# CCM_0000.net
KiCad netlist of a schematic drawn in EAGLE
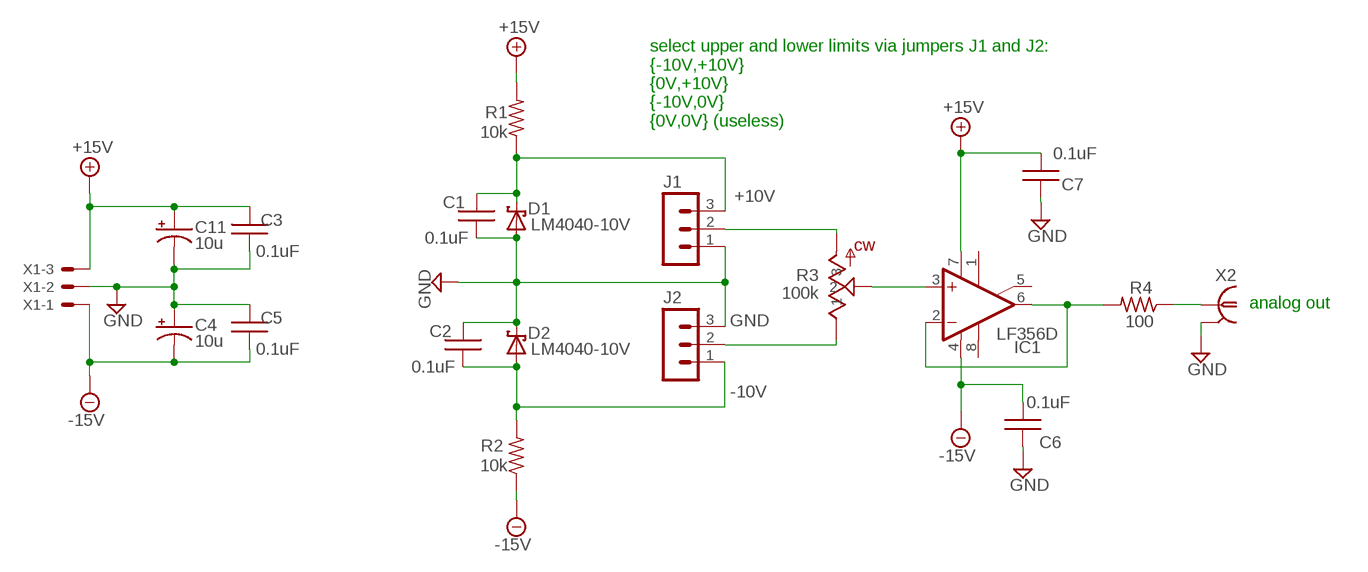
[diagram p0: schematic, sheet 1]

(export (version "E")
  (design (tool "Eeschema 10.0.6"))
  (components
    (comp (ref "C1")
      (value "0.1uF")
      (footprint "eagle-import:0603")
      (libsource (lib "eagle-import") (part "CAPACITOR0603"))
    )
    (comp (ref "C2")
      (value "0.1uF")
      (footprint "eagle-import:0603")
      (libsource (lib "eagle-import") (part "CAPACITOR0603"))
    )
    (comp (ref "C3")
      (value "0.1uF")
      (footprint "eagle-import:0603")
      (libsource (lib "eagle-import") (part "CAPACITOR0603"))
    )
    (comp (ref "C4")
      (value "10u")
      (footprint "eagle-import:EIA3216")
      (libsource (lib "eagle-import") (part "CAP_POL1206"))
    )
    (comp (ref "C5")
      (value "0.1uF")
      (footprint "eagle-import:0603")
      (libsource (lib "eagle-import") (part "CAPACITOR0603"))
    )
    (comp (ref "C6")
      (value "0.1uF")
      (footprint "eagle-import:0603")
      (libsource (lib "eagle-import") (part "CAPACITOR0603"))
    )
    (comp (ref "C7")
      (value "0.1uF")
      (footprint "eagle-import:0603")
      (libsource (lib "eagle-import") (part "CAPACITOR0603"))
    )
    (comp (ref "C11")
      (value "10u")
      (footprint "eagle-import:EIA3216")
      (libsource (lib "eagle-import") (part "CAP_POL1206"))
    )
    (comp (ref "D1")
      (value "LM4040-10V")
      (footprint "eagle-import:SOT23")
      (libsource (lib "eagle-import") (part "LM4040"))
    )
    (comp (ref "D2")
      (value "LM4040-10V")
      (footprint "eagle-import:SOT23")
      (libsource (lib "eagle-import") (part "LM4040"))
    )
    (comp (ref "IC1")
      (value "LF356D")
      (footprint "eagle-import:SO08")
      (libsource (lib "eagle-import") (part "LF356D"))
    )
    (comp (ref "J1")
      (value "MA03-1")
      (footprint "eagle-import:MA03-1")
      (libsource (lib "eagle-import") (part "MA03-1"))
    )
    (comp (ref "J2")
      (value "MA03-1")
      (footprint "eagle-import:MA03-1")
      (libsource (lib "eagle-import") (part "MA03-1"))
    )
    (comp (ref "R1")
      (value "10k")
      (footprint "eagle-import:0603")
      (libsource (lib "eagle-import") (part "RESISTOR0603"))
    )
    (comp (ref "R2")
      (value "10k")
      (footprint "eagle-import:0603")
      (libsource (lib "eagle-import") (part "RESISTOR0603"))
    )
    (comp (ref "R3")
      (value "100k")
      (footprint "eagle-import:3590")
      (libsource (lib "eagle-import") (part "TRIM_US-"))
    )
    (comp (ref "R4")
      (value "100")
      (footprint "eagle-import:0603")
      (libsource (lib "eagle-import") (part "RESISTOR0603"))
    )
    (comp (ref "X1")
      (value "22-23-2031")
      (footprint "eagle-import:22-23-2031")
      (fields (field (name "MF") "MOLEX"))
      (libsource (lib "eagle-import") (part "22-23-2031"))
    )
    (comp (ref "X2")
      (value "1-227161-0")
      (footprint "eagle-import:AMP_227161")
      (fields (field (name "MF") "TYCO ELECTRONICS") (field (name "MPN") "1-227161"))
      (libsource (lib "eagle-import") (part "?2271611--0"))
    )
  )
  (nets
    (net (code "1") (name "+15V") (class "Default")
      (node (ref "C11") (pin "A") (pinfunction "+_A") (pintype "passive"))
      (node (ref "C3") (pin "1") (pinfunction "1_1") (pintype "passive"))
      (node (ref "C7") (pin "2") (pinfunction "2_2") (pintype "passive"))
      (node (ref "IC1") (pin "7") (pinfunction "V+_7") (pintype "power_in"))
      (node (ref "R1") (pin "2") (pinfunction "2_2") (pintype "passive"))
      (node (ref "X1") (pin "3") (pinfunction "S_3") (pintype "passive"))
    )
    (net (code "2") (name "-15V") (class "Default")
      (node (ref "C4") (pin "C") (pinfunction "-_C") (pintype "passive"))
      (node (ref "C5") (pin "2") (pinfunction "2_2") (pintype "passive"))
      (node (ref "C6") (pin "2") (pinfunction "2_2") (pintype "passive"))
      (node (ref "IC1") (pin "4") (pinfunction "V-_4") (pintype "power_in"))
      (node (ref "R2") (pin "1") (pinfunction "1_1") (pintype "passive"))
      (node (ref "X1") (pin "1") (pinfunction "S_1") (pintype "passive"))
    )
    (net (code "3") (name "/+10V") (class "Default")
      (node (ref "C1") (pin "1") (pinfunction "1_1") (pintype "passive"))
      (node (ref "D1") (pin "1") (pinfunction "C_1") (pintype "passive"))
      (node (ref "J1") (pin "3") (pinfunction "3_3") (pintype "passive"))
      (node (ref "R1") (pin "1") (pinfunction "1_1") (pintype "passive"))
    )
    (net (code "4") (name "/-10V") (class "Default")
      (node (ref "C2") (pin "2") (pinfunction "2_2") (pintype "passive"))
      (node (ref "D2") (pin "2") (pinfunction "A_2") (pintype "passive"))
      (node (ref "J2") (pin "1") (pinfunction "1_1") (pintype "passive"))
      (node (ref "R2") (pin "2") (pinfunction "2_2") (pintype "passive"))
    )
    (net (code "5") (name "GND") (class "Default")
      (node (ref "C1") (pin "2") (pinfunction "2_2") (pintype "passive"))
      (node (ref "C11") (pin "C") (pinfunction "-_C") (pintype "passive"))
      (node (ref "C2") (pin "1") (pinfunction "1_1") (pintype "passive"))
      (node (ref "C3") (pin "2") (pinfunction "2_2") (pintype "passive"))
      (node (ref "C4") (pin "A") (pinfunction "+_A") (pintype "passive"))
      (node (ref "C5") (pin "1") (pinfunction "1_1") (pintype "passive"))
      (node (ref "C6") (pin "1") (pinfunction "1_1") (pintype "passive"))
      (node (ref "C7") (pin "1") (pinfunction "1_1") (pintype "passive"))
      (node (ref "D1") (pin "2") (pinfunction "A_2") (pintype "passive"))
      (node (ref "D2") (pin "1") (pinfunction "C_1") (pintype "passive"))
      (node (ref "J1") (pin "1") (pinfunction "1_1") (pintype "passive"))
      (node (ref "J2") (pin "3") (pinfunction "3_3") (pintype "passive"))
      (node (ref "X1") (pin "2") (pinfunction "S_2") (pintype "passive"))
      (node (ref "X2") (pin "2") (pinfunction "2_2") (pintype "passive"))
    )
    (net (code "6") (name "Net-(IC1-+IN)") (class "Default")
      (node (ref "IC1") (pin "3") (pinfunction "+IN_3") (pintype "input"))
      (node (ref "R3") (pin "2") (pinfunction "2_2") (pintype "passive"))
    )
    (net (code "7") (name "Net-(IC1--IN)") (class "Default")
      (node (ref "IC1") (pin "2") (pinfunction "-IN_2") (pintype "input"))
      (node (ref "IC1") (pin "6") (pinfunction "OUT_6") (pintype "output"))
      (node (ref "R4") (pin "2") (pinfunction "2_2") (pintype "passive"))
    )
    (net (code "8") (name "Net-(J1-Pad2)") (class "Default")
      (node (ref "J1") (pin "2") (pinfunction "2_2") (pintype "passive"))
      (node (ref "R3") (pin "3") (pinfunction "3_3") (pintype "passive"))
    )
    (net (code "9") (name "Net-(J2-Pad2)") (class "Default")
      (node (ref "J2") (pin "2") (pinfunction "2_2") (pintype "passive"))
      (node (ref "R3") (pin "1") (pinfunction "1_1") (pintype "passive"))
    )
    (net (code "10") (name "Net-(R4-Pad1)") (class "Default")
      (node (ref "R4") (pin "1") (pinfunction "1_1") (pintype "passive"))
      (node (ref "X2") (pin "1") (pinfunction "1_1") (pintype "passive"))
    )
    (net (code "11") (name "unconnected-(IC1-ON1-Pad1)") (class "Default")
      (node (ref "IC1") (pin "1") (pinfunction "ON1_1") (pintype "passive"))
    )
    (net (code "12") (name "unconnected-(IC1-ON2-Pad5)") (class "Default")
      (node (ref "IC1") (pin "5") (pinfunction "ON2_5") (pintype "passive"))
    )
    (net (code "13") (name "unconnected-(IC1-OPT-Pad8)") (class "Default")
      (node (ref "IC1") (pin "8") (pinfunction "OPT_8") (pintype "passive"))
    )
  )
)
